# main.net
KiCad netlist of a schematic drawn in Altium Designer
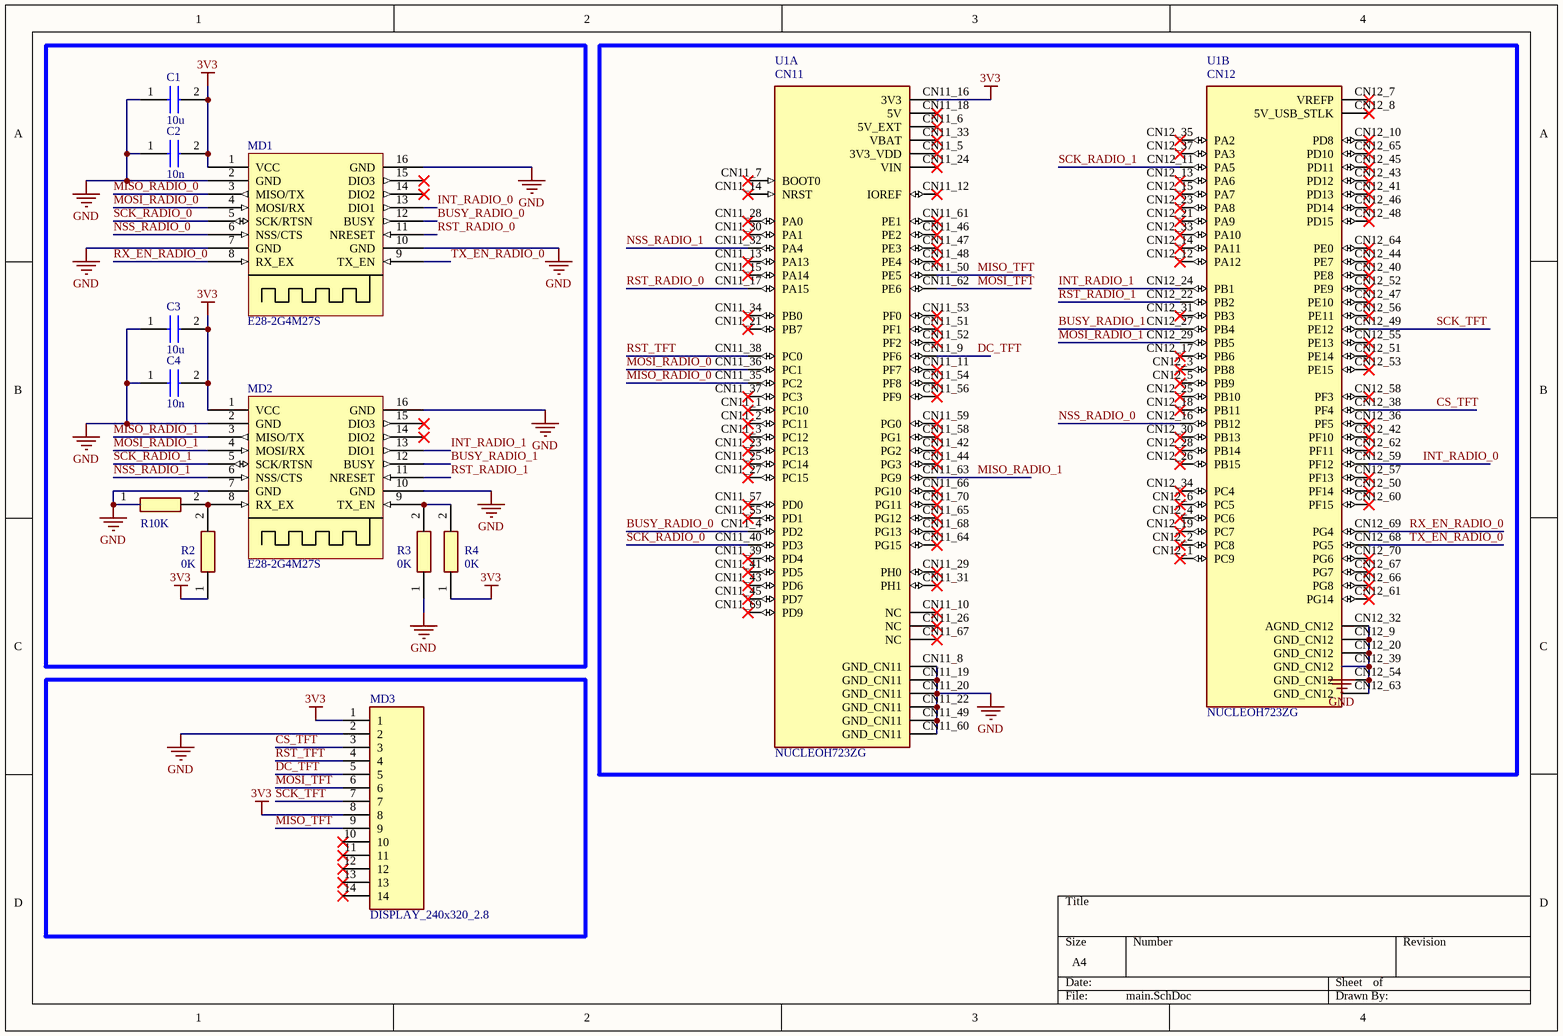
[diagram p0: main.SchDoc]

(export (version "E")
  (design (tool "Eeschema 10.0.6"))
  (components
    (comp (ref "C1")
      (value "10u")
      (footprint "roboime:CAPC1608X95N")
      (description "Capacitor")
      (fields
        (field (name "MANUFACTURER_PART_NUMBER") "C0603C104K1RACAUTO")
        (field (name "MOUSER PART NUMBER") "80-C0603C104K1RAUTO")
      )
      (libsource (lib "roboime") (part "C0603C104K1RACAUTO"))
    )
    (comp (ref "C2")
      (value "10n")
      (footprint "roboime:CAPC1608X95N")
      (description "Capacitor")
      (fields
        (field (name "MANUFACTURER_PART_NUMBER") "C0603C104K1RACAUTO")
        (field (name "MOUSER PART NUMBER") "80-C0603C104K1RAUTO")
      )
      (libsource (lib "roboime") (part "C0603C104K1RACAUTO"))
    )
    (comp (ref "C3")
      (value "10u")
      (footprint "roboime:CAPC1608X95N")
      (description "Capacitor")
      (fields
        (field (name "MANUFACTURER_PART_NUMBER") "C0603C104K1RACAUTO")
        (field (name "MOUSER PART NUMBER") "80-C0603C104K1RAUTO")
      )
      (libsource (lib "roboime") (part "C0603C104K1RACAUTO"))
    )
    (comp (ref "C4")
      (value "10n")
      (footprint "roboime:CAPC1608X95N")
      (description "Capacitor")
      (fields
        (field (name "MANUFACTURER_PART_NUMBER") "C0603C104K1RACAUTO")
        (field (name "MOUSER PART NUMBER") "80-C0603C104K1RAUTO")
      )
      (libsource (lib "roboime") (part "C0603C104K1RACAUTO"))
    )
    (comp (ref "MD1")
      (value "E28-2G4M27S")
      (footprint "roboime:E28-2G4M27S")
      (description "E28-2G4M27S Ebyte SX1280 Module")
      (libsource (lib "roboime") (part "E28-2G4M27S"))
    )
    (comp (ref "MD2")
      (value "E28-2G4M27S")
      (footprint "roboime:E28-2G4M27S")
      (description "E28-2G4M27S Ebyte SX1280 Module")
      (libsource (lib "roboime") (part "E28-2G4M27S"))
    )
    (comp (ref "MD3")
      (value "DISPLAY_240x320_2.8")
      (footprint "roboime:DISPLAY_240x320_2.8")
      (description "2.8 inch TFT Module 240×320 ILI9341 GMT028-06T")
      (fields
        (field (name "MANUFACTURER_PART_NUMBER") "M20-7821446")
        (field (name "MOUSER PART NUMBER") "855-M20-7821446")
      )
      (libsource (lib "roboime") (part "DISPLAY_240x320_2.8"))
    )
    (comp (ref "R1")
      (value "0K")
      (footprint "roboime:RESC1608X55N")
      (description "Resistor")
      (fields
        (field (name "MANUFACTURER_PART_NUMBER") "CRCW06034R70FKEAHP")
        (field (name "MOUSER PART NUMBER") "71-CRCW06034R70FKEAH")
      )
      (libsource (lib "") (part "CRCW06034R70FKEAHP_1"))
    )
    (comp (ref "R2")
      (value "0K")
      (footprint "roboime:RESC1608X55N")
      (description "Resistor")
      (fields
        (field (name "MANUFACTURER_PART_NUMBER") "CRCW06034R70FKEAHP")
        (field (name "MOUSER PART NUMBER") "71-CRCW06034R70FKEAH")
      )
      (libsource (lib "roboime") (part "CRCW06034R70FKEAHP"))
    )
    (comp (ref "R3")
      (value "0K")
      (footprint "roboime:RESC1608X55N")
      (description "Resistor")
      (fields
        (field (name "MANUFACTURER_PART_NUMBER") "CRCW06034R70FKEAHP")
        (field (name "MOUSER PART NUMBER") "71-CRCW06034R70FKEAH")
      )
      (libsource (lib "roboime") (part "CRCW06034R70FKEAHP"))
    )
    (comp (ref "R4")
      (value "0K")
      (footprint "roboime:RESC1608X55N")
      (description "Resistor")
      (fields
        (field (name "MANUFACTURER_PART_NUMBER") "CRCW06034R70FKEAHP")
        (field (name "MOUSER PART NUMBER") "71-CRCW06034R70FKEAH")
      )
      (libsource (lib "roboime") (part "CRCW06034R70FKEAHP"))
    )
    (comp (ref "U1")
      (value "NUCLEOH723ZG")
      (footprint "roboime:NEW_NUCLEO")
      (description "STM32H723ZG Nucleo-144 STM32H7 STM32 MCU 32-Bit Embedded Evaluation Board")
      (fields (field (name "MF") "STMicroelectronics"))
      (libsource (lib "roboime") (part "NUCLEOH723ZG"))
    )
  )
  (nets
    (net (code "1") (name "/BUSY_RADIO_0") (class "Default")
      (node (ref "MD1") (pin "12") (pinfunction "BUSY_12") (pintype "output"))
      (node (ref "U1") (pin "CN11_4") (pinfunction "PD2_CN11_4") (pintype "bidirectional"))
    )
    (net (code "2") (name "/BUSY_RADIO_1") (class "Default")
      (node (ref "MD2") (pin "12") (pinfunction "BUSY_12") (pintype "output"))
      (node (ref "U1") (pin "CN12_27") (pinfunction "PB4_CN12_27") (pintype "bidirectional"))
    )
    (net (code "3") (name "/CS_TFT") (class "Default")
      (node (ref "MD3") (pin "3") (pinfunction "3_3") (pintype "passive"))
      (node (ref "U1") (pin "CN12_38") (pinfunction "PF4_CN12_38") (pintype "bidirectional"))
    )
    (net (code "4") (name "/DC_TFT") (class "Default")
      (node (ref "MD3") (pin "5") (pinfunction "5_5") (pintype "passive"))
      (node (ref "U1") (pin "CN11_9") (pinfunction "PF6_CN11_9") (pintype "bidirectional"))
    )
    (net (code "5") (name "/INT_RADIO_0") (class "Default")
      (node (ref "MD1") (pin "13") (pinfunction "DIO1_13") (pintype "output"))
      (node (ref "U1") (pin "CN12_59") (pinfunction "PF12_CN12_59") (pintype "bidirectional"))
    )
    (net (code "6") (name "/INT_RADIO_1") (class "Default")
      (node (ref "MD2") (pin "13") (pinfunction "DIO1_13") (pintype "output"))
      (node (ref "U1") (pin "CN12_24") (pinfunction "PB1_CN12_24") (pintype "bidirectional"))
    )
    (net (code "7") (name "/MISO_RADIO_0") (class "Default")
      (node (ref "MD1") (pin "3") (pinfunction "MISO/TX_3") (pintype "output"))
      (node (ref "U1") (pin "CN11_35") (pinfunction "PC2_CN11_35") (pintype "bidirectional"))
    )
    (net (code "8") (name "/MISO_RADIO_1") (class "Default")
      (node (ref "MD2") (pin "3") (pinfunction "MISO/TX_3") (pintype "output"))
      (node (ref "U1") (pin "CN11_63") (pinfunction "PG9_CN11_63") (pintype "bidirectional"))
    )
    (net (code "9") (name "/MISO_TFT") (class "Default")
      (node (ref "MD3") (pin "9") (pinfunction "9_9") (pintype "passive"))
      (node (ref "U1") (pin "CN11_50") (pinfunction "PE5_CN11_50") (pintype "bidirectional"))
    )
    (net (code "10") (name "/MOSI_RADIO_0") (class "Default")
      (node (ref "MD1") (pin "4") (pinfunction "MOSI/RX_4") (pintype "input"))
      (node (ref "U1") (pin "CN11_36") (pinfunction "PC1_CN11_36") (pintype "bidirectional"))
    )
    (net (code "11") (name "/MOSI_RADIO_1") (class "Default")
      (node (ref "MD2") (pin "4") (pinfunction "MOSI/RX_4") (pintype "input"))
      (node (ref "U1") (pin "CN12_29") (pinfunction "PB5_CN12_29") (pintype "bidirectional"))
    )
    (net (code "12") (name "/MOSI_TFT") (class "Default")
      (node (ref "MD3") (pin "6") (pinfunction "6_6") (pintype "passive"))
      (node (ref "U1") (pin "CN11_62") (pinfunction "PE6_CN11_62") (pintype "bidirectional"))
    )
    (net (code "13") (name "/NSS_RADIO_0") (class "Default")
      (node (ref "MD1") (pin "6") (pinfunction "NSS/CTS_6") (pintype "input"))
      (node (ref "U1") (pin "CN12_16") (pinfunction "PB12_CN12_16") (pintype "bidirectional"))
    )
    (net (code "14") (name "/NSS_RADIO_1") (class "Default")
      (node (ref "MD2") (pin "6") (pinfunction "NSS/CTS_6") (pintype "input"))
      (node (ref "U1") (pin "CN11_32") (pinfunction "PA4_CN11_32") (pintype "bidirectional"))
    )
    (net (code "15") (name "/RST_RADIO_0") (class "Default")
      (node (ref "MD1") (pin "11") (pinfunction "NRESET_11") (pintype "input"))
      (node (ref "U1") (pin "CN11_17") (pinfunction "PA15_CN11_17") (pintype "bidirectional"))
    )
    (net (code "16") (name "/RST_RADIO_1") (class "Default")
      (node (ref "MD2") (pin "11") (pinfunction "NRESET_11") (pintype "input"))
      (node (ref "U1") (pin "CN12_22") (pinfunction "PB2_CN12_22") (pintype "bidirectional"))
    )
    (net (code "17") (name "/RST_TFT") (class "Default")
      (node (ref "MD3") (pin "4") (pinfunction "4_4") (pintype "passive"))
      (node (ref "U1") (pin "CN11_38") (pinfunction "PC0_CN11_38") (pintype "bidirectional"))
    )
    (net (code "18") (name "/RX_EN_RADIO_0") (class "Default")
      (node (ref "MD1") (pin "8") (pinfunction "RX_EX_8") (pintype "input"))
      (node (ref "U1") (pin "CN12_69") (pinfunction "PG4_CN12_69") (pintype "bidirectional"))
    )
    (net (code "19") (name "/SCK_RADIO_0") (class "Default")
      (node (ref "MD1") (pin "5") (pinfunction "SCK/RTSN_5") (pintype "bidirectional"))
      (node (ref "U1") (pin "CN11_40") (pinfunction "PD3_CN11_40") (pintype "bidirectional"))
    )
    (net (code "20") (name "/SCK_RADIO_1") (class "Default")
      (node (ref "MD2") (pin "5") (pinfunction "SCK/RTSN_5") (pintype "bidirectional"))
      (node (ref "U1") (pin "CN12_11") (pinfunction "PA5_CN12_11") (pintype "bidirectional"))
    )
    (net (code "21") (name "/SCK_TFT") (class "Default")
      (node (ref "MD3") (pin "7") (pinfunction "7_7") (pintype "passive"))
      (node (ref "U1") (pin "CN12_49") (pinfunction "PE12_CN12_49") (pintype "bidirectional"))
    )
    (net (code "22") (name "/TX_EN_RADIO_0") (class "Default")
      (node (ref "MD1") (pin "9") (pinfunction "TX_EN_9") (pintype "input"))
      (node (ref "U1") (pin "CN12_68") (pinfunction "PG5_CN12_68") (pintype "bidirectional"))
    )
    (net (code "23") (name "3V3") (class "Default")
      (node (ref "C1") (pin "2") (pinfunction "2_2") (pintype "passive"))
      (node (ref "C2") (pin "2") (pinfunction "2_2") (pintype "passive"))
      (node (ref "C3") (pin "2") (pinfunction "2_2") (pintype "passive"))
      (node (ref "C4") (pin "2") (pinfunction "2_2") (pintype "passive"))
      (node (ref "MD1") (pin "1") (pinfunction "VCC_1") (pintype "power_in"))
      (node (ref "MD2") (pin "1") (pinfunction "VCC_1") (pintype "power_in"))
      (node (ref "MD3") (pin "1") (pinfunction "1_1") (pintype "passive"))
      (node (ref "MD3") (pin "8") (pinfunction "8_8") (pintype "passive"))
      (node (ref "R2") (pin "1") (pinfunction "1_1") (pintype "passive"))
      (node (ref "R4") (pin "1") (pinfunction "1_1") (pintype "passive"))
      (node (ref "U1") (pin "CN11_16") (pinfunction "3V3_CN11_16") (pintype "power_in"))
    )
    (net (code "24") (name "GND") (class "Default")
      (node (ref "C1") (pin "1") (pinfunction "1_1") (pintype "passive"))
      (node (ref "C2") (pin "1") (pinfunction "1_1") (pintype "passive"))
      (node (ref "C3") (pin "1") (pinfunction "1_1") (pintype "passive"))
      (node (ref "C4") (pin "1") (pinfunction "1_1") (pintype "passive"))
      (node (ref "MD1") (pin "10") (pinfunction "GND_10") (pintype "power_in"))
      (node (ref "MD1") (pin "16") (pinfunction "GND_16") (pintype "power_in"))
      (node (ref "MD1") (pin "2") (pinfunction "GND_2") (pintype "power_in"))
      (node (ref "MD1") (pin "7") (pinfunction "GND_7") (pintype "power_in"))
      (node (ref "MD2") (pin "10") (pinfunction "GND_10") (pintype "power_in"))
      (node (ref "MD2") (pin "16") (pinfunction "GND_16") (pintype "power_in"))
      (node (ref "MD2") (pin "2") (pinfunction "GND_2") (pintype "power_in"))
      (node (ref "MD2") (pin "7") (pinfunction "GND_7") (pintype "power_in"))
      (node (ref "MD3") (pin "2") (pinfunction "2_2") (pintype "passive"))
      (node (ref "R1") (pin "1") (pinfunction "1_1") (pintype "passive"))
      (node (ref "R3") (pin "1") (pinfunction "1_1") (pintype "passive"))
      (node (ref "U1") (pin "CN11_19") (pinfunction "GND_CN11_CN11_19") (pintype "power_in"))
      (node (ref "U1") (pin "CN11_20") (pinfunction "GND_CN11_CN11_20") (pintype "power_in"))
      (node (ref "U1") (pin "CN11_22") (pinfunction "GND_CN11_CN11_22") (pintype "power_in"))
      (node (ref "U1") (pin "CN11_49") (pinfunction "GND_CN11_CN11_49") (pintype "power_in"))
      (node (ref "U1") (pin "CN11_60") (pinfunction "GND_CN11_CN11_60") (pintype "power_in"))
      (node (ref "U1") (pin "CN11_8") (pinfunction "GND_CN11_CN11_8") (pintype "power_in"))
      (node (ref "U1") (pin "CN12_20") (pinfunction "GND_CN12_CN12_20") (pintype "power_in"))
      (node (ref "U1") (pin "CN12_32") (pinfunction "AGND_CN12_CN12_32") (pintype "power_in"))
      (node (ref "U1") (pin "CN12_39") (pinfunction "GND_CN12_CN12_39") (pintype "power_in"))
      (node (ref "U1") (pin "CN12_54") (pinfunction "GND_CN12_CN12_54") (pintype "power_in"))
      (node (ref "U1") (pin "CN12_63") (pinfunction "GND_CN12_CN12_63") (pintype "power_in"))
      (node (ref "U1") (pin "CN12_9") (pinfunction "GND_CN12_CN12_9") (pintype "power_in"))
    )
    (net (code "25") (name "Net-(MD2-RX_EX)") (class "Default")
      (node (ref "MD2") (pin "8") (pinfunction "RX_EX_8") (pintype "input"))
      (node (ref "R1") (pin "2") (pinfunction "2_2") (pintype "passive"))
      (node (ref "R2") (pin "2") (pinfunction "2_2") (pintype "passive"))
    )
    (net (code "26") (name "Net-(MD2-TX_EN)") (class "Default")
      (node (ref "MD2") (pin "9") (pinfunction "TX_EN_9") (pintype "input"))
      (node (ref "R3") (pin "2") (pinfunction "2_2") (pintype "passive"))
      (node (ref "R4") (pin "2") (pinfunction "2_2") (pintype "passive"))
    )
    (net (code "27") (name "unconnected-(MD1-DIO2-Pad14)") (class "Default")
      (node (ref "MD1") (pin "14") (pinfunction "DIO2_14") (pintype "output+no_connect"))
    )
    (net (code "28") (name "unconnected-(MD1-DIO3-Pad15)") (class "Default")
      (node (ref "MD1") (pin "15") (pinfunction "DIO3_15") (pintype "output+no_connect"))
    )
    (net (code "29") (name "unconnected-(MD2-DIO2-Pad14)") (class "Default")
      (node (ref "MD2") (pin "14") (pinfunction "DIO2_14") (pintype "output+no_connect"))
    )
    (net (code "30") (name "unconnected-(MD2-DIO3-Pad15)") (class "Default")
      (node (ref "MD2") (pin "15") (pinfunction "DIO3_15") (pintype "output+no_connect"))
    )
    (net (code "31") (name "unconnected-(MD3-Pad10)") (class "Default")
      (node (ref "MD3") (pin "10") (pinfunction "10_10") (pintype "passive+no_connect"))
    )
    (net (code "32") (name "unconnected-(MD3-Pad11)") (class "Default")
      (node (ref "MD3") (pin "11") (pinfunction "11_11") (pintype "passive+no_connect"))
    )
    (net (code "33") (name "unconnected-(MD3-Pad12)") (class "Default")
      (node (ref "MD3") (pin "12") (pinfunction "12_12") (pintype "passive+no_connect"))
    )
    (net (code "34") (name "unconnected-(MD3-Pad13)") (class "Default")
      (node (ref "MD3") (pin "13") (pinfunction "13_13") (pintype "passive+no_connect"))
    )
    (net (code "35") (name "unconnected-(MD3-Pad14)") (class "Default")
      (node (ref "MD3") (pin "14") (pinfunction "14_14") (pintype "passive+no_connect"))
    )
    (net (code "36") (name "unconnected-(U1A-3V3_VDD-PadCN11_5)") (class "Default")
      (node (ref "U1") (pin "CN11_5") (pinfunction "3V3_VDD_CN11_5") (pintype "power_in+no_connect"))
    )
    (net (code "37") (name "unconnected-(U1A-5V-PadCN11_18)") (class "Default")
      (node (ref "U1") (pin "CN11_18") (pinfunction "5V_CN11_18") (pintype "power_in+no_connect"))
    )
    (net (code "38") (name "unconnected-(U1A-5V_EXT-PadCN11_6)") (class "Default")
      (node (ref "U1") (pin "CN11_6") (pinfunction "5V_EXT_CN11_6") (pintype "power_in+no_connect"))
    )
    (net (code "39") (name "unconnected-(U1A-BOOT0-PadCN11_7)") (class "Default")
      (node (ref "U1") (pin "CN11_7") (pinfunction "BOOT0_CN11_7") (pintype "input+no_connect"))
    )
    (net (code "40") (name "unconnected-(U1A-IOREF-PadCN11_12)") (class "Default")
      (node (ref "U1") (pin "CN11_12") (pinfunction "IOREF_CN11_12") (pintype "bidirectional+no_connect"))
    )
    (net (code "41") (name "unconnected-(U1A-NC-PadCN11_10)") (class "Default")
      (node (ref "U1") (pin "CN11_10") (pinfunction "NC_CN11_10") (pintype "passive+no_connect"))
    )
    (net (code "42") (name "unconnected-(U1A-NC-PadCN11_26)") (class "Default")
      (node (ref "U1") (pin "CN11_26") (pinfunction "NC_CN11_26") (pintype "passive+no_connect"))
    )
    (net (code "43") (name "unconnected-(U1A-NC-PadCN11_67)") (class "Default")
      (node (ref "U1") (pin "CN11_67") (pinfunction "NC_CN11_67") (pintype "passive+no_connect"))
    )
    (net (code "44") (name "unconnected-(U1A-NRST-PadCN11_14)") (class "Default")
      (node (ref "U1") (pin "CN11_14") (pinfunction "NRST_CN11_14") (pintype "input+no_connect"))
    )
    (net (code "45") (name "unconnected-(U1A-PA0-PadCN11_28)") (class "Default")
      (node (ref "U1") (pin "CN11_28") (pinfunction "PA0_CN11_28") (pintype "bidirectional+no_connect"))
    )
    (net (code "46") (name "unconnected-(U1A-PA1-PadCN11_30)") (class "Default")
      (node (ref "U1") (pin "CN11_30") (pinfunction "PA1_CN11_30") (pintype "bidirectional+no_connect"))
    )
    (net (code "47") (name "unconnected-(U1A-PA13-PadCN11_13)") (class "Default")
      (node (ref "U1") (pin "CN11_13") (pinfunction "PA13_CN11_13") (pintype "bidirectional+no_connect"))
    )
    (net (code "48") (name "unconnected-(U1A-PA14-PadCN11_15)") (class "Default")
      (node (ref "U1") (pin "CN11_15") (pinfunction "PA14_CN11_15") (pintype "bidirectional+no_connect"))
    )
    (net (code "49") (name "unconnected-(U1A-PB0-PadCN11_34)") (class "Default")
      (node (ref "U1") (pin "CN11_34") (pinfunction "PB0_CN11_34") (pintype "bidirectional+no_connect"))
    )
    (net (code "50") (name "unconnected-(U1A-PB7-PadCN11_21)") (class "Default")
      (node (ref "U1") (pin "CN11_21") (pinfunction "PB7_CN11_21") (pintype "bidirectional+no_connect"))
    )
    (net (code "51") (name "unconnected-(U1A-PC3-PadCN11_37)") (class "Default")
      (node (ref "U1") (pin "CN11_37") (pinfunction "PC3_CN11_37") (pintype "bidirectional+no_connect"))
    )
    (net (code "52") (name "unconnected-(U1A-PC10-PadCN11_1)") (class "Default")
      (node (ref "U1") (pin "CN11_1") (pinfunction "PC10_CN11_1") (pintype "bidirectional+no_connect"))
    )
    (net (code "53") (name "unconnected-(U1A-PC11-PadCN11_2)") (class "Default")
      (node (ref "U1") (pin "CN11_2") (pinfunction "PC11_CN11_2") (pintype "bidirectional+no_connect"))
    )
    (net (code "54") (name "unconnected-(U1A-PC12-PadCN11_3)") (class "Default")
      (node (ref "U1") (pin "CN11_3") (pinfunction "PC12_CN11_3") (pintype "bidirectional+no_connect"))
    )
    (net (code "55") (name "unconnected-(U1A-PC13-PadCN11_23)") (class "Default")
      (node (ref "U1") (pin "CN11_23") (pinfunction "PC13_CN11_23") (pintype "bidirectional+no_connect"))
    )
    (net (code "56") (name "unconnected-(U1A-PC14-PadCN11_25)") (class "Default")
      (node (ref "U1") (pin "CN11_25") (pinfunction "PC14_CN11_25") (pintype "bidirectional+no_connect"))
    )
    (net (code "57") (name "unconnected-(U1A-PC15-PadCN11_27)") (class "Default")
      (node (ref "U1") (pin "CN11_27") (pinfunction "PC15_CN11_27") (pintype "bidirectional+no_connect"))
    )
    (net (code "58") (name "unconnected-(U1A-PD0-PadCN11_57)") (class "Default")
      (node (ref "U1") (pin "CN11_57") (pinfunction "PD0_CN11_57") (pintype "bidirectional+no_connect"))
    )
    (net (code "59") (name "unconnected-(U1A-PD1-PadCN11_55)") (class "Default")
      (node (ref "U1") (pin "CN11_55") (pinfunction "PD1_CN11_55") (pintype "bidirectional+no_connect"))
    )
    (net (code "60") (name "unconnected-(U1A-PD4-PadCN11_39)") (class "Default")
      (node (ref "U1") (pin "CN11_39") (pinfunction "PD4_CN11_39") (pintype "bidirectional+no_connect"))
    )
    (net (code "61") (name "unconnected-(U1A-PD5-PadCN11_41)") (class "Default")
      (node (ref "U1") (pin "CN11_41") (pinfunction "PD5_CN11_41") (pintype "bidirectional+no_connect"))
    )
    (net (code "62") (name "unconnected-(U1A-PD6-PadCN11_43)") (class "Default")
      (node (ref "U1") (pin "CN11_43") (pinfunction "PD6_CN11_43") (pintype "bidirectional+no_connect"))
    )
    (net (code "63") (name "unconnected-(U1A-PD7-PadCN11_45)") (class "Default")
      (node (ref "U1") (pin "CN11_45") (pinfunction "PD7_CN11_45") (pintype "bidirectional+no_connect"))
    )
    (net (code "64") (name "unconnected-(U1A-PD9-PadCN11_69)") (class "Default")
      (node (ref "U1") (pin "CN11_69") (pinfunction "PD9_CN11_69") (pintype "bidirectional+no_connect"))
    )
    (net (code "65") (name "unconnected-(U1A-PE1-PadCN11_61)") (class "Default")
      (node (ref "U1") (pin "CN11_61") (pinfunction "PE1_CN11_61") (pintype "bidirectional+no_connect"))
    )
    (net (code "66") (name "unconnected-(U1A-PE2-PadCN11_46)") (class "Default")
      (node (ref "U1") (pin "CN11_46") (pinfunction "PE2_CN11_46") (pintype "bidirectional+no_connect"))
    )
    (net (code "67") (name "unconnected-(U1A-PE3-PadCN11_47)") (class "Default")
      (node (ref "U1") (pin "CN11_47") (pinfunction "PE3_CN11_47") (pintype "bidirectional+no_connect"))
    )
    (net (code "68") (name "unconnected-(U1A-PE4-PadCN11_48)") (class "Default")
      (node (ref "U1") (pin "CN11_48") (pinfunction "PE4_CN11_48") (pintype "bidirectional+no_connect"))
    )
    (net (code "69") (name "unconnected-(U1A-PF0-PadCN11_53)") (class "Default")
      (node (ref "U1") (pin "CN11_53") (pinfunction "PF0_CN11_53") (pintype "bidirectional+no_connect"))
    )
    (net (code "70") (name "unconnected-(U1A-PF1-PadCN11_51)") (class "Default")
      (node (ref "U1") (pin "CN11_51") (pinfunction "PF1_CN11_51") (pintype "bidirectional+no_connect"))
    )
    (net (code "71") (name "unconnected-(U1A-PF2-PadCN11_52)") (class "Default")
      (node (ref "U1") (pin "CN11_52") (pinfunction "PF2_CN11_52") (pintype "bidirectional+no_connect"))
    )
    (net (code "72") (name "unconnected-(U1A-PF7-PadCN11_11)") (class "Default")
      (node (ref "U1") (pin "CN11_11") (pinfunction "PF7_CN11_11") (pintype "bidirectional+no_connect"))
    )
    (net (code "73") (name "unconnected-(U1A-PF8-PadCN11_54)") (class "Default")
      (node (ref "U1") (pin "CN11_54") (pinfunction "PF8_CN11_54") (pintype "bidirectional+no_connect"))
    )
    (net (code "74") (name "unconnected-(U1A-PF9-PadCN11_56)") (class "Default")
      (node (ref "U1") (pin "CN11_56") (pinfunction "PF9_CN11_56") (pintype "bidirectional+no_connect"))
    )
    (net (code "75") (name "unconnected-(U1A-PG0-PadCN11_59)") (class "Default")
      (node (ref "U1") (pin "CN11_59") (pinfunction "PG0_CN11_59") (pintype "bidirectional+no_connect"))
    )
    (net (code "76") (name "unconnected-(U1A-PG1-PadCN11_58)") (class "Default")
      (node (ref "U1") (pin "CN11_58") (pinfunction "PG1_CN11_58") (pintype "bidirectional+no_connect"))
    )
    (net (code "77") (name "unconnected-(U1A-PG2-PadCN11_42)") (class "Default")
      (node (ref "U1") (pin "CN11_42") (pinfunction "PG2_CN11_42") (pintype "bidirectional+no_connect"))
    )
    (net (code "78") (name "unconnected-(U1A-PG3-PadCN11_44)") (class "Default")
      (node (ref "U1") (pin "CN11_44") (pinfunction "PG3_CN11_44") (pintype "bidirectional+no_connect"))
    )
    (net (code "79") (name "unconnected-(U1A-PG10-PadCN11_66)") (class "Default")
      (node (ref "U1") (pin "CN11_66") (pinfunction "PG10_CN11_66") (pintype "bidirectional+no_connect"))
    )
    (net (code "80") (name "unconnected-(U1A-PG11-PadCN11_70)") (class "Default")
      (node (ref "U1") (pin "CN11_70") (pinfunction "PG11_CN11_70") (pintype "bidirectional+no_connect"))
    )
    (net (code "81") (name "unconnected-(U1A-PG12-PadCN11_65)") (class "Default")
      (node (ref "U1") (pin "CN11_65") (pinfunction "PG12_CN11_65") (pintype "bidirectional+no_connect"))
    )
    (net (code "82") (name "unconnected-(U1A-PG13-PadCN11_68)") (class "Default")
      (node (ref "U1") (pin "CN11_68") (pinfunction "PG13_CN11_68") (pintype "bidirectional+no_connect"))
    )
    (net (code "83") (name "unconnected-(U1A-PG15-PadCN11_64)") (class "Default")
      (node (ref "U1") (pin "CN11_64") (pinfunction "PG15_CN11_64") (pintype "bidirectional+no_connect"))
    )
    (net (code "84") (name "unconnected-(U1A-PH0-PadCN11_29)") (class "Default")
      (node (ref "U1") (pin "CN11_29") (pinfunction "PH0_CN11_29") (pintype "bidirectional+no_connect"))
    )
    (net (code "85") (name "unconnected-(U1A-PH1-PadCN11_31)") (class "Default")
      (node (ref "U1") (pin "CN11_31") (pinfunction "PH1_CN11_31") (pintype "bidirectional+no_connect"))
    )
    (net (code "86") (name "unconnected-(U1A-VBAT-PadCN11_33)") (class "Default")
      (node (ref "U1") (pin "CN11_33") (pinfunction "VBAT_CN11_33") (pintype "power_in+no_connect"))
    )
    (net (code "87") (name "unconnected-(U1A-VIN-PadCN11_24)") (class "Default")
      (node (ref "U1") (pin "CN11_24") (pinfunction "VIN_CN11_24") (pintype "power_in+no_connect"))
    )
    (net (code "88") (name "unconnected-(U1B-5V_USB_STLK-PadCN12_8)") (class "Default")
      (node (ref "U1") (pin "CN12_8") (pinfunction "5V_USB_STLK_CN12_8") (pintype "power_in+no_connect"))
    )
    (net (code "89") (name "unconnected-(U1B-PA2-PadCN12_35)") (class "Default")
      (node (ref "U1") (pin "CN12_35") (pinfunction "PA2_CN12_35") (pintype "bidirectional+no_connect"))
    )
    (net (code "90") (name "unconnected-(U1B-PA3-PadCN12_37)") (class "Default")
      (node (ref "U1") (pin "CN12_37") (pinfunction "PA3_CN12_37") (pintype "bidirectional+no_connect"))
    )
    (net (code "91") (name "unconnected-(U1B-PA6-PadCN12_13)") (class "Default")
      (node (ref "U1") (pin "CN12_13") (pinfunction "PA6_CN12_13") (pintype "bidirectional+no_connect"))
    )
    (net (code "92") (name "unconnected-(U1B-PA7-PadCN12_15)") (class "Default")
      (node (ref "U1") (pin "CN12_15") (pinfunction "PA7_CN12_15") (pintype "bidirectional+no_connect"))
    )
    (net (code "93") (name "unconnected-(U1B-PA8-PadCN12_23)") (class "Default")
      (node (ref "U1") (pin "CN12_23") (pinfunction "PA8_CN12_23") (pintype "bidirectional+no_connect"))
    )
    (net (code "94") (name "unconnected-(U1B-PA9-PadCN12_21)") (class "Default")
      (node (ref "U1") (pin "CN12_21") (pinfunction "PA9_CN12_21") (pintype "bidirectional+no_connect"))
    )
    (net (code "95") (name "unconnected-(U1B-PA10-PadCN12_33)") (class "Default")
      (node (ref "U1") (pin "CN12_33") (pinfunction "PA10_CN12_33") (pintype "bidirectional+no_connect"))
    )
    (net (code "96") (name "unconnected-(U1B-PA11-PadCN12_14)") (class "Default")
      (node (ref "U1") (pin "CN12_14") (pinfunction "PA11_CN12_14") (pintype "bidirectional+no_connect"))
    )
    (net (code "97") (name "unconnected-(U1B-PA12-PadCN12_12)") (class "Default")
      (node (ref "U1") (pin "CN12_12") (pinfunction "PA12_CN12_12") (pintype "bidirectional+no_connect"))
    )
    (net (code "98") (name "unconnected-(U1B-PB3-PadCN12_31)") (class "Default")
      (node (ref "U1") (pin "CN12_31") (pinfunction "PB3_CN12_31") (pintype "bidirectional+no_connect"))
    )
    (net (code "99") (name "unconnected-(U1B-PB6-PadCN12_17)") (class "Default")
      (node (ref "U1") (pin "CN12_17") (pinfunction "PB6_CN12_17") (pintype "bidirectional+no_connect"))
    )
    (net (code "100") (name "unconnected-(U1B-PB8-PadCN12_3)") (class "Default")
      (node (ref "U1") (pin "CN12_3") (pinfunction "PB8_CN12_3") (pintype "bidirectional+no_connect"))
    )
    (net (code "101") (name "unconnected-(U1B-PB9-PadCN12_5)") (class "Default")
      (node (ref "U1") (pin "CN12_5") (pinfunction "PB9_CN12_5") (pintype "bidirectional+no_connect"))
    )
    (net (code "102") (name "unconnected-(U1B-PB10-PadCN12_25)") (class "Default")
      (node (ref "U1") (pin "CN12_25") (pinfunction "PB10_CN12_25") (pintype "bidirectional+no_connect"))
    )
    (net (code "103") (name "unconnected-(U1B-PB11-PadCN12_18)") (class "Default")
      (node (ref "U1") (pin "CN12_18") (pinfunction "PB11_CN12_18") (pintype "bidirectional+no_connect"))
    )
    (net (code "104") (name "unconnected-(U1B-PB13-PadCN12_30)") (class "Default")
      (node (ref "U1") (pin "CN12_30") (pinfunction "PB13_CN12_30") (pintype "bidirectional+no_connect"))
    )
    (net (code "105") (name "unconnected-(U1B-PB14-PadCN12_28)") (class "Default")
      (node (ref "U1") (pin "CN12_28") (pinfunction "PB14_CN12_28") (pintype "bidirectional+no_connect"))
    )
    (net (code "106") (name "unconnected-(U1B-PB15-PadCN12_26)") (class "Default")
      (node (ref "U1") (pin "CN12_26") (pinfunction "PB15_CN12_26") (pintype "bidirectional+no_connect"))
    )
    (net (code "107") (name "unconnected-(U1B-PC4-PadCN12_34)") (class "Default")
      (node (ref "U1") (pin "CN12_34") (pinfunction "PC4_CN12_34") (pintype "bidirectional+no_connect"))
    )
    (net (code "108") (name "unconnected-(U1B-PC5-PadCN12_6)") (class "Default")
      (node (ref "U1") (pin "CN12_6") (pinfunction "PC5_CN12_6") (pintype "bidirectional+no_connect"))
    )
    (net (code "109") (name "unconnected-(U1B-PC6-PadCN12_4)") (class "Default")
      (node (ref "U1") (pin "CN12_4") (pinfunction "PC6_CN12_4") (pintype "bidirectional+no_connect"))
    )
    (net (code "110") (name "unconnected-(U1B-PC7-PadCN12_19)") (class "Default")
      (node (ref "U1") (pin "CN12_19") (pinfunction "PC7_CN12_19") (pintype "bidirectional+no_connect"))
    )
    (net (code "111") (name "unconnected-(U1B-PC8-PadCN12_2)") (class "Default")
      (node (ref "U1") (pin "CN12_2") (pinfunction "PC8_CN12_2") (pintype "bidirectional+no_connect"))
    )
    (net (code "112") (name "unconnected-(U1B-PC9-PadCN12_1)") (class "Default")
      (node (ref "U1") (pin "CN12_1") (pinfunction "PC9_CN12_1") (pintype "bidirectional+no_connect"))
    )
    (net (code "113") (name "unconnected-(U1B-PD8-PadCN12_10)") (class "Default")
      (node (ref "U1") (pin "CN12_10") (pinfunction "PD8_CN12_10") (pintype "bidirectional+no_connect"))
    )
    (net (code "114") (name "unconnected-(U1B-PD10-PadCN12_65)") (class "Default")
      (node (ref "U1") (pin "CN12_65") (pinfunction "PD10_CN12_65") (pintype "bidirectional+no_connect"))
    )
    (net (code "115") (name "unconnected-(U1B-PD11-PadCN12_45)") (class "Default")
      (node (ref "U1") (pin "CN12_45") (pinfunction "PD11_CN12_45") (pintype "bidirectional+no_connect"))
    )
    (net (code "116") (name "unconnected-(U1B-PD12-PadCN12_43)") (class "Default")
      (node (ref "U1") (pin "CN12_43") (pinfunction "PD12_CN12_43") (pintype "bidirectional+no_connect"))
    )
    (net (code "117") (name "unconnected-(U1B-PD13-PadCN12_41)") (class "Default")
      (node (ref "U1") (pin "CN12_41") (pinfunction "PD13_CN12_41") (pintype "bidirectional+no_connect"))
    )
    (net (code "118") (name "unconnected-(U1B-PD14-PadCN12_46)") (class "Default")
      (node (ref "U1") (pin "CN12_46") (pinfunction "PD14_CN12_46") (pintype "bidirectional+no_connect"))
    )
    (net (code "119") (name "unconnected-(U1B-PD15-PadCN12_48)") (class "Default")
      (node (ref "U1") (pin "CN12_48") (pinfunction "PD15_CN12_48") (pintype "bidirectional+no_connect"))
    )
    (net (code "120") (name "unconnected-(U1B-PE0-PadCN12_64)") (class "Default")
      (node (ref "U1") (pin "CN12_64") (pinfunction "PE0_CN12_64") (pintype "bidirectional+no_connect"))
    )
    (net (code "121") (name "unconnected-(U1B-PE7-PadCN12_44)") (class "Default")
      (node (ref "U1") (pin "CN12_44") (pinfunction "PE7_CN12_44") (pintype "bidirectional+no_connect"))
    )
    (net (code "122") (name "unconnected-(U1B-PE8-PadCN12_40)") (class "Default")
      (node (ref "U1") (pin "CN12_40") (pinfunction "PE8_CN12_40") (pintype "bidirectional+no_connect"))
    )
    (net (code "123") (name "unconnected-(U1B-PE9-PadCN12_52)") (class "Default")
      (node (ref "U1") (pin "CN12_52") (pinfunction "PE9_CN12_52") (pintype "bidirectional+no_connect"))
    )
    (net (code "124") (name "unconnected-(U1B-PE10-PadCN12_47)") (class "Default")
      (node (ref "U1") (pin "CN12_47") (pinfunction "PE10_CN12_47") (pintype "bidirectional+no_connect"))
    )
    (net (code "125") (name "unconnected-(U1B-PE11-PadCN12_56)") (class "Default")
      (node (ref "U1") (pin "CN12_56") (pinfunction "PE11_CN12_56") (pintype "bidirectional+no_connect"))
    )
    (net (code "126") (name "unconnected-(U1B-PE13-PadCN12_55)") (class "Default")
      (node (ref "U1") (pin "CN12_55") (pinfunction "PE13_CN12_55") (pintype "bidirectional+no_connect"))
    )
    (net (code "127") (name "unconnected-(U1B-PE14-PadCN12_51)") (class "Default")
      (node (ref "U1") (pin "CN12_51") (pinfunction "PE14_CN12_51") (pintype "bidirectional+no_connect"))
    )
    (net (code "128") (name "unconnected-(U1B-PE15-PadCN12_53)") (class "Default")
      (node (ref "U1") (pin "CN12_53") (pinfunction "PE15_CN12_53") (pintype "bidirectional+no_connect"))
    )
    (net (code "129") (name "unconnected-(U1B-PF3-PadCN12_58)") (class "Default")
      (node (ref "U1") (pin "CN12_58") (pinfunction "PF3_CN12_58") (pintype "bidirectional+no_connect"))
    )
    (net (code "130") (name "unconnected-(U1B-PF5-PadCN12_36)") (class "Default")
      (node (ref "U1") (pin "CN12_36") (pinfunction "PF5_CN12_36") (pintype "bidirectional+no_connect"))
    )
    (net (code "131") (name "unconnected-(U1B-PF10-PadCN12_42)") (class "Default")
      (node (ref "U1") (pin "CN12_42") (pinfunction "PF10_CN12_42") (pintype "bidirectional+no_connect"))
    )
    (net (code "132") (name "unconnected-(U1B-PF11-PadCN12_62)") (class "Default")
      (node (ref "U1") (pin "CN12_62") (pinfunction "PF11_CN12_62") (pintype "bidirectional+no_connect"))
    )
    (net (code "133") (name "unconnected-(U1B-PF13-PadCN12_57)") (class "Default")
      (node (ref "U1") (pin "CN12_57") (pinfunction "PF13_CN12_57") (pintype "bidirectional+no_connect"))
    )
    (net (code "134") (name "unconnected-(U1B-PF14-PadCN12_50)") (class "Default")
      (node (ref "U1") (pin "CN12_50") (pinfunction "PF14_CN12_50") (pintype "bidirectional+no_connect"))
    )
    (net (code "135") (name "unconnected-(U1B-PF15-PadCN12_60)") (class "Default")
      (node (ref "U1") (pin "CN12_60") (pinfunction "PF15_CN12_60") (pintype "bidirectional+no_connect"))
    )
    (net (code "136") (name "unconnected-(U1B-PG6-PadCN12_70)") (class "Default")
      (node (ref "U1") (pin "CN12_70") (pinfunction "PG6_CN12_70") (pintype "bidirectional+no_connect"))
    )
    (net (code "137") (name "unconnected-(U1B-PG7-PadCN12_67)") (class "Default")
      (node (ref "U1") (pin "CN12_67") (pinfunction "PG7_CN12_67") (pintype "bidirectional+no_connect"))
    )
    (net (code "138") (name "unconnected-(U1B-PG8-PadCN12_66)") (class "Default")
      (node (ref "U1") (pin "CN12_66") (pinfunction "PG8_CN12_66") (pintype "bidirectional+no_connect"))
    )
    (net (code "139") (name "unconnected-(U1B-PG14-PadCN12_61)") (class "Default")
      (node (ref "U1") (pin "CN12_61") (pinfunction "PG14_CN12_61") (pintype "bidirectional+no_connect"))
    )
    (net (code "140") (name "unconnected-(U1B-VREFP-PadCN12_7)") (class "Default")
      (node (ref "U1") (pin "CN12_7") (pinfunction "VREFP_CN12_7") (pintype "power_in+no_connect"))
    )
  )
)
